# 12_TO_3V3_VOLTAGE_DIVIDER.net
KiCad netlist of a schematic drawn in Altium Designer
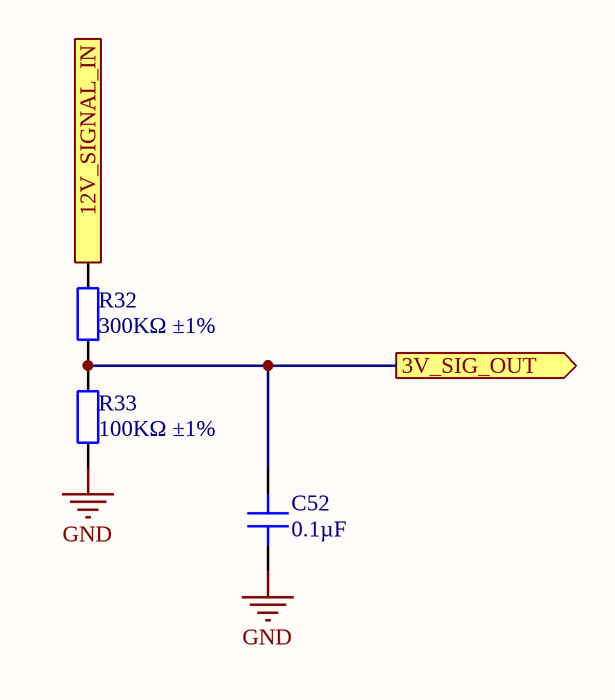
[diagram p0: 12_TO_3V3_VOLTAGE_DIVIDER.SchDoc]

(export (version "E")
  (design (tool "Eeschema 10.0.6"))
  (components
    (comp (ref "C52")
      (value "0.1µF")
      (footprint "CAP 0402_1005")
      (description "CAP CER 0402 0.1UF 16V X7R 10%")
      (fields (field (name "PART NUMBER") "C0402C104K4RECAUTO") (field (name "MANUFACTURER") "KEMET"))
      (libsource (lib "CAL") (part "Capacitor"))
    )
    (comp (ref "R32")
      (value "300KΩ ±1%")
      (footprint "0402_R")
      (description "Chip resistor")
      (fields (field (name "MANUFACTURER") "Uniroyal Elec") (field (name "PARTNUMBER") "0402WGF3003TCE"))
      (libsource (lib "Miscellaneous Devices LC") (part "0402 300K (3003) 1%"))
    )
    (comp (ref "R33")
      (value "100KΩ ±1%")
      (footprint "0402_R")
      (description "Chip resistor")
      (fields (field (name "MANUFACTURER") "Uniroyal Elec") (field (name "PARTNUMBER") "0402WGF1003TCE"))
      (libsource (lib "Miscellaneous Devices LC") (part "0402 100K (1003) 1%"))
    )
  )
  (nets
    (net (code "1") (name "/3V_SIG_OUT") (class "Default")
      (node (ref "C52") (pin "2") (pinfunction "2_2") (pintype "passive"))
      (node (ref "R32") (pin "1") (pinfunction "1_1") (pintype "passive"))
      (node (ref "R33") (pin "2") (pinfunction "2_2") (pintype "passive"))
    )
    (net (code "2") (name "/12V_SIGNAL_IN") (class "Default")
      (node (ref "R32") (pin "2") (pinfunction "2_2") (pintype "passive"))
    )
    (net (code "3") (name "GND") (class "Default")
      (node (ref "C52") (pin "1") (pinfunction "1_1") (pintype "passive"))
      (node (ref "R33") (pin "1") (pinfunction "1_1") (pintype "passive"))
    )
  )
)
